# TripleClockGenerator.net
KiCad netlist of a schematic drawn in EAGLE
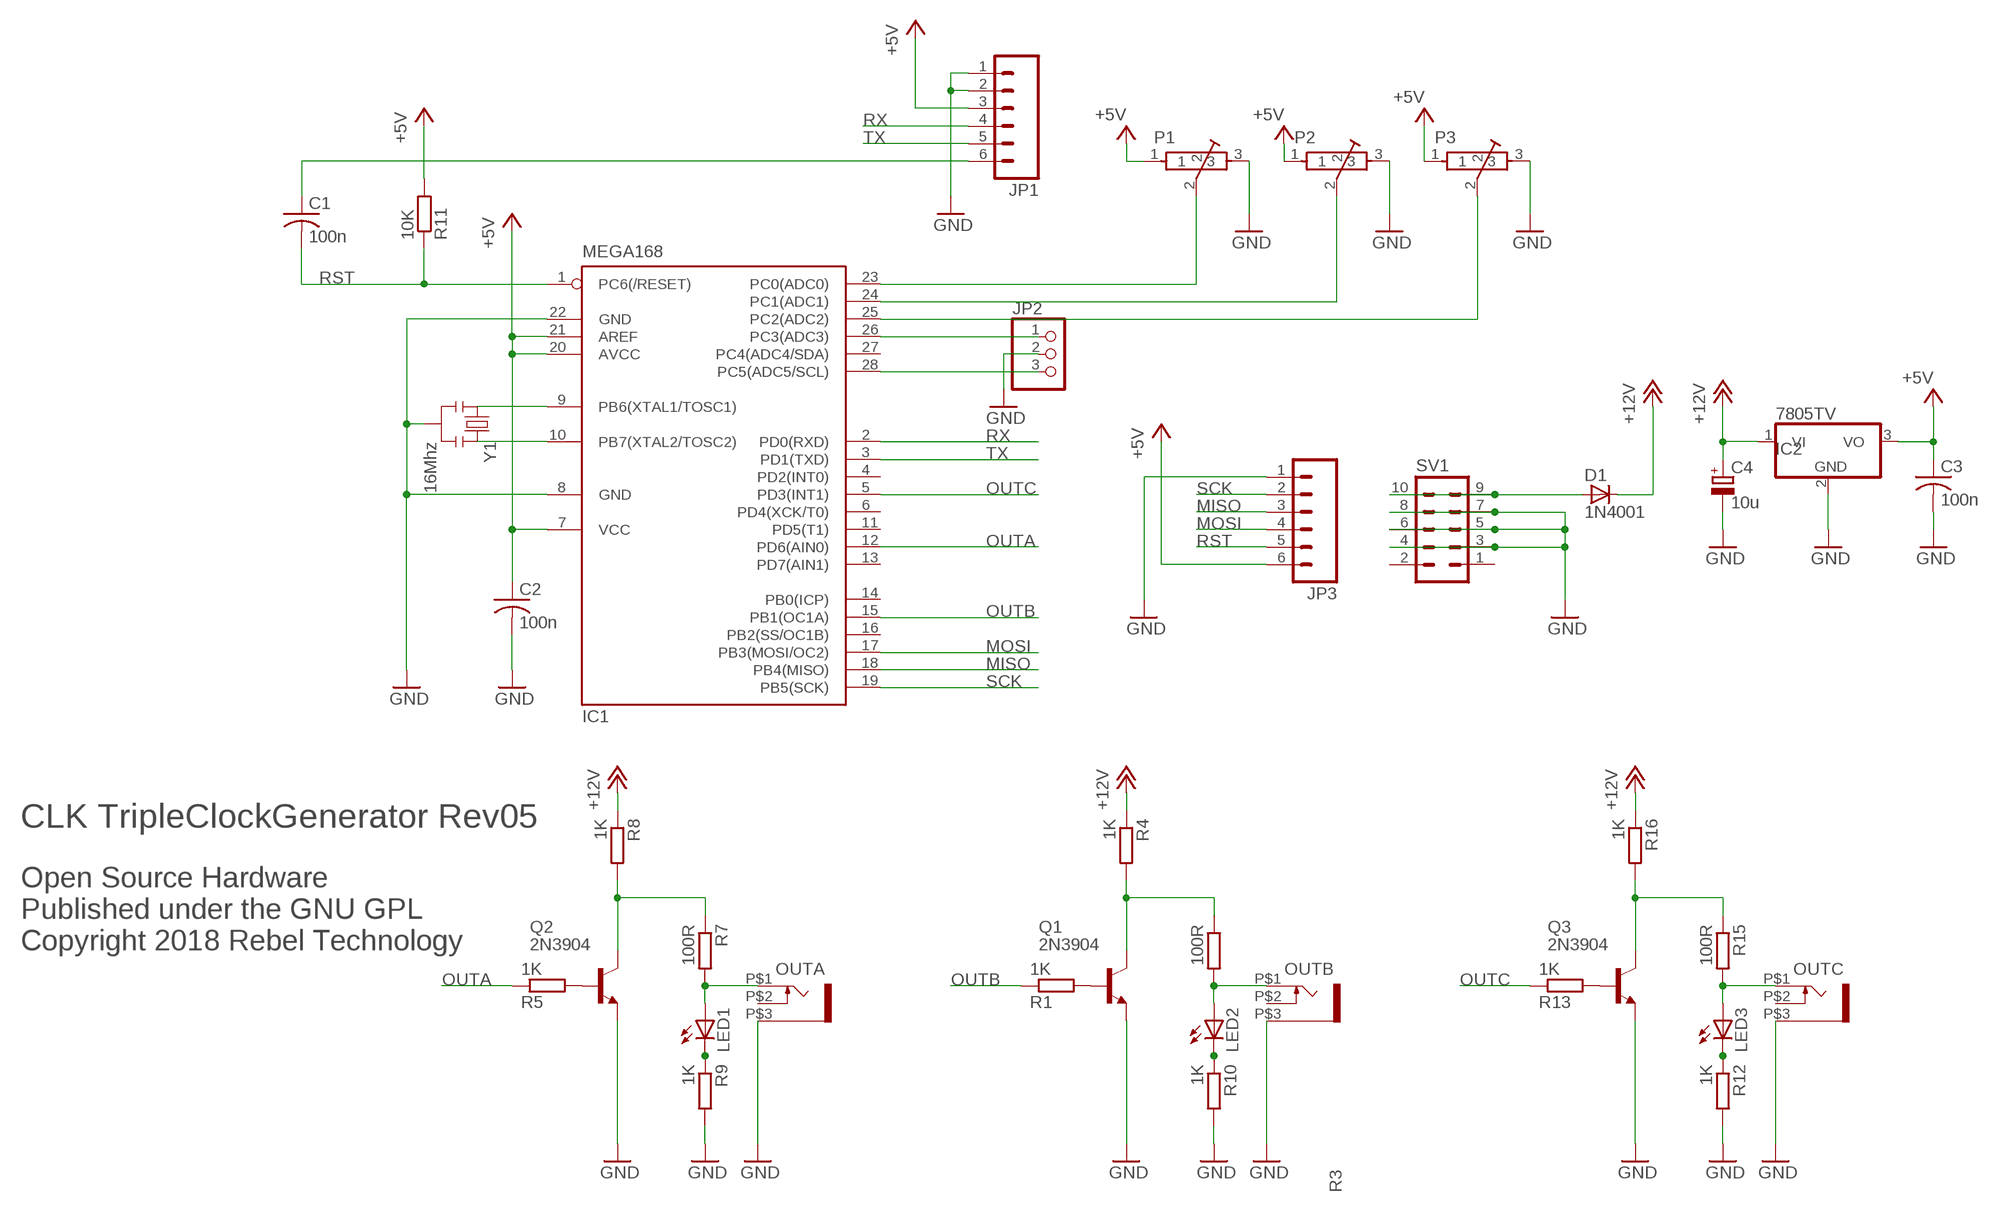
[diagram p0: schematic, sheet 1]

(export (version "E")
  (design (tool "Eeschema 10.0.6"))
  (components
    (comp (ref "C1")
      (value "100n")
      (footprint "eagle-import:C050-024X044")
      (libsource (lib "eagle-import") (part "C-US050-024X044"))
    )
    (comp (ref "C2")
      (value "100n")
      (footprint "eagle-import:C050-024X044")
      (libsource (lib "eagle-import") (part "C-US050-024X044"))
    )
    (comp (ref "C3")
      (value "100n")
      (footprint "eagle-import:C050-024X044")
      (libsource (lib "eagle-import") (part "C-US050-024X044"))
    )
    (comp (ref "C4")
      (value "10u")
      (footprint "eagle-import:E5-6")
      (libsource (lib "eagle-import") (part "CPOL-EUE5-6"))
    )
    (comp (ref "D1")
      (value "1N4001")
      (footprint "eagle-import:DIODE-1N4001")
      (libsource (lib "eagle-import") (part "DIODE1N4001"))
    )
    (comp (ref "IC1")
      (value "MEGA168")
      (footprint "eagle-import:DIL28-3")
      (libsource (lib "eagle-import") (part "MEGA8-P"))
    )
    (comp (ref "IC2")
      (value "7805TV")
      (footprint "eagle-import:TO220V")
      (libsource (lib "eagle-import") (part "78TV05"))
    )
    (comp (ref "JP1")
      (value "M06SIP")
      (footprint "eagle-import:1X06")
      (libsource (lib "eagle-import") (part "M06SIP"))
    )
    (comp (ref "JP2")
      (value "PINHD-1X3")
      (footprint "eagle-import:1X03")
      (libsource (lib "eagle-import") (part "PINHD-1X3"))
    )
    (comp (ref "JP3")
      (value "M06SIP")
      (footprint "eagle-import:1X06")
      (libsource (lib "eagle-import") (part "M06SIP"))
    )
    (comp (ref "LED1")
      (value "LED3MM")
      (footprint "eagle-import:LED3MM")
      (libsource (lib "eagle-import") (part "LED3MM"))
    )
    (comp (ref "LED2")
      (value "LED3MM")
      (footprint "eagle-import:LED3MM")
      (libsource (lib "eagle-import") (part "LED3MM"))
    )
    (comp (ref "LED3")
      (value "LED3MM")
      (footprint "eagle-import:LED3MM")
      (libsource (lib "eagle-import") (part "LED3MM"))
    )
    (comp (ref "OUTA")
      (value "JACK-UJ-3502-RSLOT")
      (footprint "eagle-import:UJ-3502-R-SLOT")
      (libsource (lib "eagle-import") (part "JACK-UJ-3502-RSLOT"))
    )
    (comp (ref "OUTB")
      (value "JACK-UJ-3502-RSLOT")
      (footprint "eagle-import:UJ-3502-R-SLOT")
      (libsource (lib "eagle-import") (part "JACK-UJ-3502-RSLOT"))
    )
    (comp (ref "OUTC")
      (value "JACK-UJ-3502-RSLOT")
      (footprint "eagle-import:UJ-3502-R-SLOT")
      (libsource (lib "eagle-import") (part "JACK-UJ-3502-RSLOT"))
    )
    (comp (ref "P1")
      (value "POT-BOURNS-PTD901")
      (footprint "eagle-import:POT-BOURNS-PTD901")
      (libsource (lib "eagle-import") (part "POT-BOURNS-PTD901"))
    )
    (comp (ref "P2")
      (value "POT-BOURNS-PTD901")
      (footprint "eagle-import:POT-BOURNS-PTD901")
      (libsource (lib "eagle-import") (part "POT-BOURNS-PTD901"))
    )
    (comp (ref "P3")
      (value "POT-BOURNS-PTD901")
      (footprint "eagle-import:POT-BOURNS-PTD901")
      (libsource (lib "eagle-import") (part "POT-BOURNS-PTD901"))
    )
    (comp (ref "Q1")
      (value "2N3904")
      (footprint "eagle-import:TO92")
      (libsource (lib "eagle-import") (part "2N3904"))
    )
    (comp (ref "Q2")
      (value "2N3904")
      (footprint "eagle-import:TO92")
      (libsource (lib "eagle-import") (part "2N3904"))
    )
    (comp (ref "Q3")
      (value "2N3904")
      (footprint "eagle-import:TO92")
      (libsource (lib "eagle-import") (part "2N3904"))
    )
    (comp (ref "R1")
      (value "1K")
      (footprint "eagle-import:0204_7")
      (libsource (lib "eagle-import") (part "R-EU_0204/7"))
    )
    (comp (ref "R3")
      (value "100R")
      (footprint "eagle-import:0204_7")
      (libsource (lib "eagle-import") (part "R-EU_0204/7"))
    )
    (comp (ref "R4")
      (value "1K")
      (footprint "eagle-import:0204_7")
      (libsource (lib "eagle-import") (part "R-EU_0204/7"))
    )
    (comp (ref "R5")
      (value "1K")
      (footprint "eagle-import:0204_7")
      (libsource (lib "eagle-import") (part "R-EU_0204/7"))
    )
    (comp (ref "R7")
      (value "100R")
      (footprint "eagle-import:0204_7")
      (libsource (lib "eagle-import") (part "R-EU_0204/7"))
    )
    (comp (ref "R8")
      (value "1K")
      (footprint "eagle-import:0204_7")
      (libsource (lib "eagle-import") (part "R-EU_0204/7"))
    )
    (comp (ref "R9")
      (value "1K")
      (footprint "eagle-import:0204_7")
      (libsource (lib "eagle-import") (part "R-EU_0204/7"))
    )
    (comp (ref "R10")
      (value "1K")
      (footprint "eagle-import:0204_7")
      (libsource (lib "eagle-import") (part "R-EU_0204/7"))
    )
    (comp (ref "R11")
      (value "10K")
      (footprint "eagle-import:0204_7")
      (libsource (lib "eagle-import") (part "R-EU_0204/7"))
    )
    (comp (ref "R12")
      (value "1K")
      (footprint "eagle-import:0204_7")
      (libsource (lib "eagle-import") (part "R-EU_0204/7"))
    )
    (comp (ref "R13")
      (value "1K")
      (footprint "eagle-import:0204_7")
      (libsource (lib "eagle-import") (part "R-EU_0204/7"))
    )
    (comp (ref "R15")
      (value "100R")
      (footprint "eagle-import:0204_7")
      (libsource (lib "eagle-import") (part "R-EU_0204/7"))
    )
    (comp (ref "R16")
      (value "1K")
      (footprint "eagle-import:0204_7")
      (libsource (lib "eagle-import") (part "R-EU_0204/7"))
    )
    (comp (ref "SV1")
      (value "MA05-2")
      (footprint "eagle-import:MA05-2")
      (libsource (lib "eagle-import") (part "MA05-2"))
    )
    (comp (ref "Y1")
      (value "16Mhz")
      (footprint "eagle-import:RESONATOR-PTH")
      (libsource (lib "eagle-import") (part "RESONATORPTH"))
    )
  )
  (nets
    (net (code "1") (name "+5V") (class "Default")
      (node (ref "C2") (pin "1") (pinfunction "1_1") (pintype "passive"))
      (node (ref "C3") (pin "1") (pinfunction "1_1") (pintype "passive"))
      (node (ref "IC1") (pin "20") (pinfunction "AVCC_20") (pintype "power_in"))
      (node (ref "IC1") (pin "21") (pinfunction "AREF_21") (pintype "passive"))
      (node (ref "IC1") (pin "7") (pinfunction "VCC_7") (pintype "power_in"))
      (node (ref "IC2") (pin "3") (pinfunction "VO_3") (pintype "passive"))
      (node (ref "JP1") (pin "3") (pinfunction "3_3") (pintype "passive"))
      (node (ref "JP3") (pin "6") (pinfunction "6_6") (pintype "passive"))
      (node (ref "P1") (pin "1") (pinfunction "1_1") (pintype "bidirectional"))
      (node (ref "P2") (pin "1") (pinfunction "1_1") (pintype "bidirectional"))
      (node (ref "P3") (pin "1") (pinfunction "1_1") (pintype "bidirectional"))
      (node (ref "R11") (pin "2") (pinfunction "2_2") (pintype "passive"))
    )
    (net (code "2") (name "+12V") (class "Default")
      (node (ref "C4") (pin "+") (pinfunction "+_+") (pintype "passive"))
      (node (ref "D1") (pin "C") (pinfunction "C_C") (pintype "passive"))
      (node (ref "IC2") (pin "1") (pinfunction "VI_1") (pintype "input"))
      (node (ref "R16") (pin "1") (pinfunction "1_1") (pintype "passive"))
      (node (ref "R4") (pin "1") (pinfunction "1_1") (pintype "passive"))
      (node (ref "R8") (pin "1") (pinfunction "1_1") (pintype "passive"))
    )
    (net (code "3") (name "/MISO") (class "Default")
      (node (ref "IC1") (pin "18") (pinfunction "PB4(MISO)_18") (pintype "bidirectional"))
      (node (ref "JP3") (pin "3") (pinfunction "3_3") (pintype "passive"))
    )
    (net (code "4") (name "/MOSI") (class "Default")
      (node (ref "IC1") (pin "17") (pinfunction "PB3(MOSI/OC2)_17") (pintype "bidirectional"))
      (node (ref "JP3") (pin "4") (pinfunction "4_4") (pintype "passive"))
    )
    (net (code "5") (name "/OUTA") (class "Default")
      (node (ref "IC1") (pin "12") (pinfunction "PD6(AIN0)_12") (pintype "bidirectional"))
      (node (ref "R5") (pin "1") (pinfunction "1_1") (pintype "passive"))
    )
    (net (code "6") (name "/OUTB") (class "Default")
      (node (ref "IC1") (pin "15") (pinfunction "PB1(OC1A)_15") (pintype "bidirectional"))
      (node (ref "R1") (pin "1") (pinfunction "1_1") (pintype "passive"))
    )
    (net (code "7") (name "/OUTC") (class "Default")
      (node (ref "IC1") (pin "5") (pinfunction "PD3(INT1)_5") (pintype "bidirectional"))
      (node (ref "R13") (pin "1") (pinfunction "1_1") (pintype "passive"))
    )
    (net (code "8") (name "/RST") (class "Default")
      (node (ref "C1") (pin "2") (pinfunction "2_2") (pintype "passive"))
      (node (ref "IC1") (pin "1") (pinfunction "PC6(/RESET)_1") (pintype "bidirectional"))
      (node (ref "JP3") (pin "5") (pinfunction "5_5") (pintype "passive"))
      (node (ref "R11") (pin "1") (pinfunction "1_1") (pintype "passive"))
    )
    (net (code "9") (name "/RX") (class "Default")
      (node (ref "IC1") (pin "2") (pinfunction "PD0(RXD)_2") (pintype "bidirectional"))
      (node (ref "JP1") (pin "4") (pinfunction "4_4") (pintype "passive"))
    )
    (net (code "10") (name "/SCK") (class "Default")
      (node (ref "IC1") (pin "19") (pinfunction "PB5(SCK)_19") (pintype "bidirectional"))
      (node (ref "JP3") (pin "2") (pinfunction "2_2") (pintype "passive"))
    )
    (net (code "11") (name "/TX") (class "Default")
      (node (ref "IC1") (pin "3") (pinfunction "PD1(TXD)_3") (pintype "bidirectional"))
      (node (ref "JP1") (pin "5") (pinfunction "5_5") (pintype "passive"))
    )
    (net (code "12") (name "GND") (class "Default")
      (node (ref "C2") (pin "2") (pinfunction "2_2") (pintype "passive"))
      (node (ref "C3") (pin "2") (pinfunction "2_2") (pintype "passive"))
      (node (ref "C4") (pin "-") (pinfunction "-_-") (pintype "passive"))
      (node (ref "IC1") (pin "22") (pinfunction "GND_22") (pintype "power_in"))
      (node (ref "IC1") (pin "8") (pinfunction "GND_8") (pintype "power_in"))
      (node (ref "IC2") (pin "2") (pinfunction "GND_2") (pintype "passive"))
      (node (ref "JP1") (pin "1") (pinfunction "1_1") (pintype "passive"))
      (node (ref "JP1") (pin "2") (pinfunction "2_2") (pintype "passive"))
      (node (ref "JP2") (pin "2") (pinfunction "2_2") (pintype "passive"))
      (node (ref "JP3") (pin "1") (pinfunction "1_1") (pintype "passive"))
      (node (ref "OUTA") (pin "P$3") (pinfunction "SLEEVE_P$3") (pintype "passive"))
      (node (ref "OUTB") (pin "P$3") (pinfunction "SLEEVE_P$3") (pintype "passive"))
      (node (ref "OUTC") (pin "P$3") (pinfunction "SLEEVE_P$3") (pintype "passive"))
      (node (ref "P1") (pin "3") (pinfunction "3_3") (pintype "bidirectional"))
      (node (ref "P2") (pin "3") (pinfunction "3_3") (pintype "bidirectional"))
      (node (ref "P3") (pin "3") (pinfunction "3_3") (pintype "bidirectional"))
      (node (ref "Q1") (pin "3") (pinfunction "E_3") (pintype "passive"))
      (node (ref "Q2") (pin "3") (pinfunction "E_3") (pintype "passive"))
      (node (ref "Q3") (pin "3") (pinfunction "E_3") (pintype "passive"))
      (node (ref "R10") (pin "2") (pinfunction "2_2") (pintype "passive"))
      (node (ref "R12") (pin "2") (pinfunction "2_2") (pintype "passive"))
      (node (ref "R9") (pin "2") (pinfunction "2_2") (pintype "passive"))
      (node (ref "SV1") (pin "3") (pinfunction "3_3") (pintype "passive"))
      (node (ref "SV1") (pin "4") (pinfunction "4_4") (pintype "passive"))
      (node (ref "SV1") (pin "5") (pinfunction "5_5") (pintype "passive"))
      (node (ref "SV1") (pin "6") (pinfunction "6_6") (pintype "passive"))
      (node (ref "SV1") (pin "7") (pinfunction "7_7") (pintype "passive"))
      (node (ref "SV1") (pin "8") (pinfunction "8_8") (pintype "passive"))
      (node (ref "Y1") (pin "2") (pinfunction "2_2") (pintype "passive"))
    )
    (net (code "13") (name "Net-(C1-Pad1)") (class "Default")
      (node (ref "C1") (pin "1") (pinfunction "1_1") (pintype "passive"))
      (node (ref "JP1") (pin "6") (pinfunction "6_6") (pintype "passive"))
    )
    (net (code "14") (name "Net-(D1-PadA)") (class "Default")
      (node (ref "D1") (pin "A") (pinfunction "A_A") (pintype "passive"))
      (node (ref "SV1") (pin "10") (pinfunction "10_10") (pintype "passive"))
      (node (ref "SV1") (pin "9") (pinfunction "9_9") (pintype "passive"))
    )
    (net (code "15") (name "Net-(IC1-PB6(XTAL1{slash}TOSC1))") (class "Default")
      (node (ref "IC1") (pin "9") (pinfunction "PB6(XTAL1/TOSC1)_9") (pintype "bidirectional"))
      (node (ref "Y1") (pin "1") (pinfunction "1_1") (pintype "passive"))
    )
    (net (code "16") (name "Net-(IC1-PB7(XTAL2{slash}TOSC2))") (class "Default")
      (node (ref "IC1") (pin "10") (pinfunction "PB7(XTAL2/TOSC2)_10") (pintype "bidirectional"))
      (node (ref "Y1") (pin "3") (pinfunction "3_3") (pintype "passive"))
    )
    (net (code "17") (name "Net-(IC1-PC0(ADC0))") (class "Default")
      (node (ref "IC1") (pin "23") (pinfunction "PC0(ADC0)_23") (pintype "bidirectional"))
      (node (ref "P1") (pin "2") (pinfunction "2_2") (pintype "bidirectional"))
    )
    (net (code "18") (name "Net-(IC1-PC1(ADC1))") (class "Default")
      (node (ref "IC1") (pin "24") (pinfunction "PC1(ADC1)_24") (pintype "bidirectional"))
      (node (ref "P2") (pin "2") (pinfunction "2_2") (pintype "bidirectional"))
    )
    (net (code "19") (name "Net-(IC1-PC2(ADC2))") (class "Default")
      (node (ref "IC1") (pin "25") (pinfunction "PC2(ADC2)_25") (pintype "bidirectional"))
      (node (ref "P3") (pin "2") (pinfunction "2_2") (pintype "bidirectional"))
    )
    (net (code "20") (name "Net-(IC1-PC3(ADC3))") (class "Default")
      (node (ref "IC1") (pin "26") (pinfunction "PC3(ADC3)_26") (pintype "bidirectional"))
      (node (ref "JP2") (pin "1") (pinfunction "1_1") (pintype "passive"))
    )
    (net (code "21") (name "Net-(IC1-PC5(ADC5{slash}SCL))") (class "Default")
      (node (ref "IC1") (pin "28") (pinfunction "PC5(ADC5/SCL)_28") (pintype "bidirectional"))
      (node (ref "JP2") (pin "3") (pinfunction "3_3") (pintype "passive"))
    )
    (net (code "22") (name "Net-(LED1-C)") (class "Default")
      (node (ref "LED1") (pin "K") (pinfunction "C_K") (pintype "passive"))
      (node (ref "R9") (pin "1") (pinfunction "1_1") (pintype "passive"))
    )
    (net (code "23") (name "Net-(LED2-C)") (class "Default")
      (node (ref "LED2") (pin "K") (pinfunction "C_K") (pintype "passive"))
      (node (ref "R10") (pin "1") (pinfunction "1_1") (pintype "passive"))
    )
    (net (code "24") (name "Net-(LED3-C)") (class "Default")
      (node (ref "LED3") (pin "K") (pinfunction "C_K") (pintype "passive"))
      (node (ref "R12") (pin "1") (pinfunction "1_1") (pintype "passive"))
    )
    (net (code "25") (name "Net-(OUTA-TIP)") (class "Default")
      (node (ref "LED1") (pin "A") (pinfunction "A_A") (pintype "passive"))
      (node (ref "OUTA") (pin "P$1") (pinfunction "TIP_P$1") (pintype "passive"))
      (node (ref "R7") (pin "2") (pinfunction "2_2") (pintype "passive"))
    )
    (net (code "26") (name "Net-(OUTB-TIP)") (class "Default")
      (node (ref "LED2") (pin "A") (pinfunction "A_A") (pintype "passive"))
      (node (ref "OUTB") (pin "P$1") (pinfunction "TIP_P$1") (pintype "passive"))
      (node (ref "R3") (pin "2") (pinfunction "2_2") (pintype "passive"))
    )
    (net (code "27") (name "Net-(OUTC-TIP)") (class "Default")
      (node (ref "LED3") (pin "A") (pinfunction "A_A") (pintype "passive"))
      (node (ref "OUTC") (pin "P$1") (pinfunction "TIP_P$1") (pintype "passive"))
      (node (ref "R15") (pin "2") (pinfunction "2_2") (pintype "passive"))
    )
    (net (code "28") (name "Net-(Q1-B)") (class "Default")
      (node (ref "Q1") (pin "2") (pinfunction "B_2") (pintype "passive"))
      (node (ref "R1") (pin "2") (pinfunction "2_2") (pintype "passive"))
    )
    (net (code "29") (name "Net-(Q1-C)") (class "Default")
      (node (ref "Q1") (pin "1") (pinfunction "C_1") (pintype "passive"))
      (node (ref "R3") (pin "1") (pinfunction "1_1") (pintype "passive"))
      (node (ref "R4") (pin "2") (pinfunction "2_2") (pintype "passive"))
    )
    (net (code "30") (name "Net-(Q2-B)") (class "Default")
      (node (ref "Q2") (pin "2") (pinfunction "B_2") (pintype "passive"))
      (node (ref "R5") (pin "2") (pinfunction "2_2") (pintype "passive"))
    )
    (net (code "31") (name "Net-(Q2-C)") (class "Default")
      (node (ref "Q2") (pin "1") (pinfunction "C_1") (pintype "passive"))
      (node (ref "R7") (pin "1") (pinfunction "1_1") (pintype "passive"))
      (node (ref "R8") (pin "2") (pinfunction "2_2") (pintype "passive"))
    )
    (net (code "32") (name "Net-(Q3-B)") (class "Default")
      (node (ref "Q3") (pin "2") (pinfunction "B_2") (pintype "passive"))
      (node (ref "R13") (pin "2") (pinfunction "2_2") (pintype "passive"))
    )
    (net (code "33") (name "Net-(Q3-C)") (class "Default")
      (node (ref "Q3") (pin "1") (pinfunction "C_1") (pintype "passive"))
      (node (ref "R15") (pin "1") (pinfunction "1_1") (pintype "passive"))
      (node (ref "R16") (pin "2") (pinfunction "2_2") (pintype "passive"))
    )
    (net (code "34") (name "unconnected-(IC1-PB0(ICP)-Pad14)") (class "Default")
      (node (ref "IC1") (pin "14") (pinfunction "PB0(ICP)_14") (pintype "bidirectional"))
    )
    (net (code "35") (name "unconnected-(IC1-PB2(SS{slash}OC1B)-Pad16)") (class "Default")
      (node (ref "IC1") (pin "16") (pinfunction "PB2(SS/OC1B)_16") (pintype "bidirectional"))
    )
    (net (code "36") (name "unconnected-(IC1-PC4(ADC4{slash}SDA)-Pad27)") (class "Default")
      (node (ref "IC1") (pin "27") (pinfunction "PC4(ADC4/SDA)_27") (pintype "bidirectional"))
    )
    (net (code "37") (name "unconnected-(IC1-PD2(INT0)-Pad4)") (class "Default")
      (node (ref "IC1") (pin "4") (pinfunction "PD2(INT0)_4") (pintype "bidirectional"))
    )
    (net (code "38") (name "unconnected-(IC1-PD4(XCK{slash}T0)-Pad6)") (class "Default")
      (node (ref "IC1") (pin "6") (pinfunction "PD4(XCK/T0)_6") (pintype "bidirectional"))
    )
    (net (code "39") (name "unconnected-(IC1-PD5(T1)-Pad11)") (class "Default")
      (node (ref "IC1") (pin "11") (pinfunction "PD5(T1)_11") (pintype "bidirectional"))
    )
    (net (code "40") (name "unconnected-(IC1-PD7(AIN1)-Pad13)") (class "Default")
      (node (ref "IC1") (pin "13") (pinfunction "PD7(AIN1)_13") (pintype "bidirectional"))
    )
    (net (code "41") (name "unconnected-(OUTA-SW-PadP$2)") (class "Default")
      (node (ref "OUTA") (pin "P$2") (pinfunction "SW_P$2") (pintype "passive"))
    )
    (net (code "42") (name "unconnected-(OUTB-SW-PadP$2)") (class "Default")
      (node (ref "OUTB") (pin "P$2") (pinfunction "SW_P$2") (pintype "passive"))
    )
    (net (code "43") (name "unconnected-(OUTC-SW-PadP$2)") (class "Default")
      (node (ref "OUTC") (pin "P$2") (pinfunction "SW_P$2") (pintype "passive"))
    )
    (net (code "44") (name "unconnected-(SV1-Pad1)") (class "Default")
      (node (ref "SV1") (pin "1") (pinfunction "1_1") (pintype "passive"))
    )
    (net (code "45") (name "unconnected-(SV1-Pad2)") (class "Default")
      (node (ref "SV1") (pin "2") (pinfunction "2_2") (pintype "passive"))
    )
  )
)
